# Glucose_Meter_Rev1.net
KiCad netlist of a schematic drawn in EAGLE
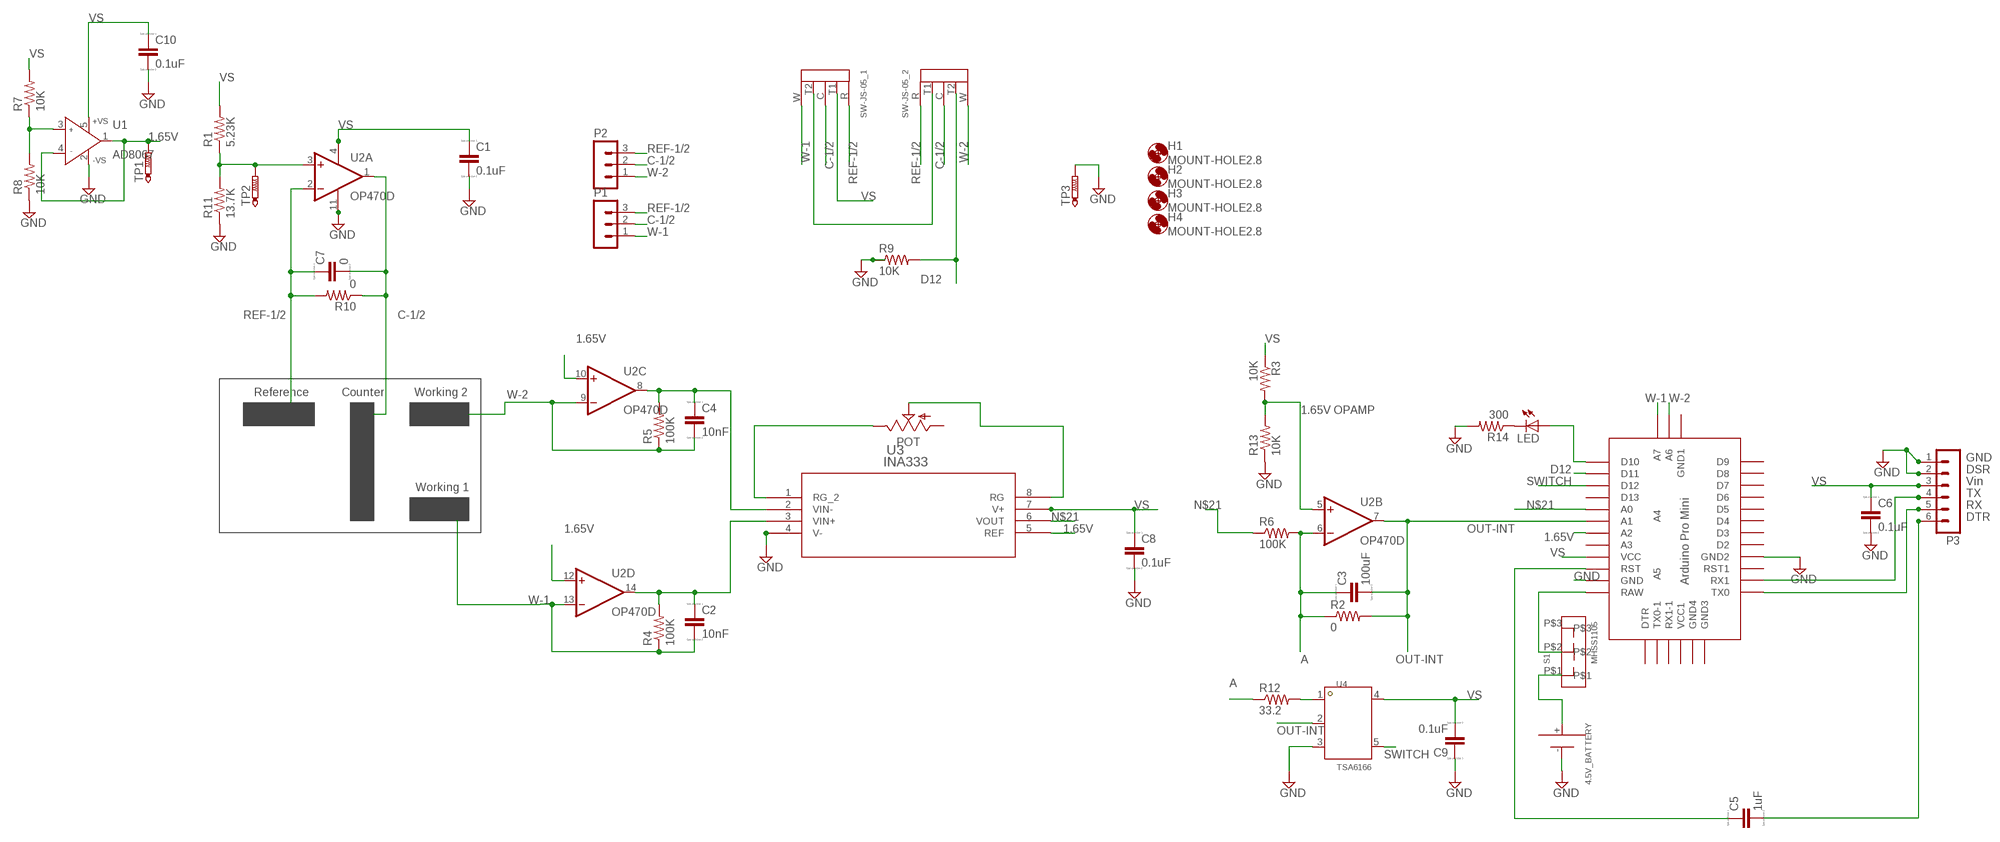
[diagram p0: schematic, sheet 1]

(export (version "E")
  (design (tool "Eeschema 10.0.6"))
  (components
    (comp (ref "4.5V_BATTERY")
      (value "BC3AAAPC")
      (footprint "eagle-import:BC3AAAPC")
      (libsource (lib "eagle-import") (part "BC3AAAPC"))
    )
    (comp (ref "C1")
      (value "0.1uF")
      (footprint "eagle-import:C0805")
      (libsource (lib "eagle-import") (part "C"))
    )
    (comp (ref "C2")
      (value "10nF")
      (footprint "eagle-import:C0805")
      (libsource (lib "eagle-import") (part "C"))
    )
    (comp (ref "C3")
      (value "100uF")
      (footprint "eagle-import:C1210")
      (libsource (lib "eagle-import") (part "CC1210"))
    )
    (comp (ref "C4")
      (value "10nF")
      (footprint "eagle-import:C0805")
      (libsource (lib "eagle-import") (part "C"))
    )
    (comp (ref "C5")
      (value "1uF")
      (footprint "eagle-import:C0805")
      (libsource (lib "eagle-import") (part "C"))
    )
    (comp (ref "C6")
      (value "0.1uF")
      (footprint "eagle-import:C0805")
      (libsource (lib "eagle-import") (part "C"))
    )
    (comp (ref "C7") (value "0") (footprint "eagle-import:C0805") (libsource (lib "eagle-import") (part "C")))
    (comp (ref "C8")
      (value "0.1uF")
      (footprint "eagle-import:C0805")
      (libsource (lib "eagle-import") (part "C"))
    )
    (comp (ref "C9")
      (value "0.1uF")
      (footprint "eagle-import:C0805")
      (libsource (lib "eagle-import") (part "C"))
    )
    (comp (ref "C10")
      (value "0.1uF")
      (footprint "eagle-import:C0805")
      (libsource (lib "eagle-import") (part "C"))
    )
    (comp (ref "H1")
      (value "MOUNT-HOLE2.8")
      (footprint "eagle-import:2,8")
      (libsource (lib "eagle-import") (part "MOUNT-HOLE2.8"))
    )
    (comp (ref "H2")
      (value "MOUNT-HOLE2.8")
      (footprint "eagle-import:2,8")
      (libsource (lib "eagle-import") (part "MOUNT-HOLE2.8"))
    )
    (comp (ref "H3")
      (value "MOUNT-HOLE2.8")
      (footprint "eagle-import:2,8")
      (libsource (lib "eagle-import") (part "MOUNT-HOLE2.8"))
    )
    (comp (ref "H4")
      (value "MOUNT-HOLE2.8")
      (footprint "eagle-import:2,8")
      (libsource (lib "eagle-import") (part "MOUNT-HOLE2.8"))
    )
    (comp (ref "LED")
      (value "LED3MM")
      (footprint "eagle-import:LED3MM")
      (libsource (lib "eagle-import") (part "LED3MM"))
    )
    (comp (ref "P1")
      (value "MA03-1")
      (footprint "eagle-import:MA03-1")
      (libsource (lib "eagle-import") (part "MA03-1"))
    )
    (comp (ref "P2")
      (value "MA03-1")
      (footprint "eagle-import:MA03-1")
      (libsource (lib "eagle-import") (part "MA03-1"))
    )
    (comp (ref "P3")
      (value "MA06-1")
      (footprint "eagle-import:MA06-1")
      (libsource (lib "eagle-import") (part "MA06-1"))
    )
    (comp (ref "POT")
      (value "TRIM_US-RJ9W")
      (footprint "eagle-import:RJ9W")
      (libsource (lib "eagle-import") (part "TRIM_US-RJ9W"))
    )
    (comp (ref "R1")
      (value "5.23K")
      (footprint "eagle-import:R0805")
      (libsource (lib "eagle-import") (part "R-US_R0805"))
    )
    (comp (ref "R2")
      (value "0")
      (footprint "eagle-import:R0805")
      (libsource (lib "eagle-import") (part "R-US_R0805"))
    )
    (comp (ref "R3")
      (value "10K")
      (footprint "eagle-import:R0805")
      (libsource (lib "eagle-import") (part "R-US_R0805"))
    )
    (comp (ref "R4")
      (value "100K")
      (footprint "eagle-import:R0805")
      (libsource (lib "eagle-import") (part "R-US_R0805"))
    )
    (comp (ref "R5")
      (value "100K")
      (footprint "eagle-import:R0805")
      (libsource (lib "eagle-import") (part "R-US_R0805"))
    )
    (comp (ref "R6")
      (value "100K")
      (footprint "eagle-import:R0805")
      (libsource (lib "eagle-import") (part "R-US_R0805"))
    )
    (comp (ref "R7")
      (value "10K")
      (footprint "eagle-import:R0805")
      (libsource (lib "eagle-import") (part "R-US_R0805"))
    )
    (comp (ref "R8")
      (value "10K")
      (footprint "eagle-import:R0805")
      (libsource (lib "eagle-import") (part "R-US_R0805"))
    )
    (comp (ref "R9")
      (value "10K")
      (footprint "eagle-import:R0805")
      (libsource (lib "eagle-import") (part "R-US_R0805"))
    )
    (comp (ref "R10")
      (value "0")
      (footprint "eagle-import:R0805")
      (libsource (lib "eagle-import") (part "R-US_R0805"))
    )
    (comp (ref "R11")
      (value "13.7K")
      (footprint "eagle-import:R0805")
      (libsource (lib "eagle-import") (part "R-US_R0805"))
    )
    (comp (ref "R12")
      (value "33.2")
      (footprint "eagle-import:R0805")
      (libsource (lib "eagle-import") (part "R-US_R0805"))
    )
    (comp (ref "R13")
      (value "10K")
      (footprint "eagle-import:R0805")
      (libsource (lib "eagle-import") (part "R-US_R0805"))
    )
    (comp (ref "R14")
      (value "300")
      (footprint "eagle-import:R0805")
      (libsource (lib "eagle-import") (part "R-US_R0805"))
    )
    (comp (ref "S1")
      (value "MHSS1105")
      (footprint "eagle-import:MHSS1105")
      (libsource (lib "eagle-import") (part "MHSS1105"))
    )
    (comp (ref "SW-JS-05_1")
      (value "SW-JS-05")
      (footprint "eagle-import:SW-JS-05")
      (libsource (lib "eagle-import") (part "SW-JS-05"))
    )
    (comp (ref "SW-JS-05_2")
      (value "SW-JS-05")
      (footprint "eagle-import:SW-JS-05")
      (libsource (lib "eagle-import") (part "SW-JS-05"))
    )
    (comp (ref "TP1")
      (value "PTR1PAD1-13")
      (footprint "eagle-import:P1-13")
      (libsource (lib "eagle-import") (part "PTR1PAD1-13"))
    )
    (comp (ref "TP2")
      (value "PTR1PAD1-13")
      (footprint "eagle-import:P1-13")
      (libsource (lib "eagle-import") (part "PTR1PAD1-13"))
    )
    (comp (ref "TP3")
      (value "PTR1PAD1-13")
      (footprint "eagle-import:P1-13")
      (libsource (lib "eagle-import") (part "PTR1PAD1-13"))
    )
    (comp (ref "U$1")
      (value "ABK-PRO-MINI")
      (footprint "eagle-import:ABK-PRO-MINI")
      (libsource (lib "eagle-import") (part "ABK-PRO-MINI"))
    )
    (comp (ref "U1")
      (value "AD8067")
      (footprint "eagle-import:SOT23-5")
      (fields (field (name "MF") "ALTERA CORPORATION") (field (name "MPN") "AD8067ARTZ-REEL7"))
      (libsource (lib "eagle-import") (part "AD8067"))
    )
    (comp (ref "U2")
      (value "OP470D")
      (footprint "eagle-import:SO14")
      (libsource (lib "eagle-import") (part "OP470D"))
    )
    (comp (ref "U3")
      (value "INA333")
      (footprint "eagle-import:DGK8")
      (fields
        (field (name "MANUFACTURER") "Texas Instruments")
        (field (name "MANUFACTURER_PART_NUMBER") "ina333_dgk_8")
      )
      (libsource (lib "eagle-import") (part "INA333_DGK_8"))
    )
    (comp (ref "U4")
      (value "TSA6166")
      (footprint "eagle-import:SOT23-5")
      (libsource (lib "eagle-import") (part "TSA6166"))
    )
  )
  (nets
    (net (code "1") (name "/1.65V") (class "Default")
      (node (ref "TP1") (pin "TP") (pinfunction "TP_TP") (pintype "input"))
      (node (ref "U$1") (pin "A2") (pinfunction "A2_A2") (pintype "bidirectional"))
      (node (ref "U1") (pin "1") (pinfunction "OUT_1") (pintype "output"))
      (node (ref "U1") (pin "4") (pinfunction "IN-_4") (pintype "input"))
      (node (ref "U2") (pin "10") (pinfunction "+IN_10") (pintype "input"))
      (node (ref "U2") (pin "12") (pinfunction "+IN_12") (pintype "input"))
      (node (ref "U3") (pin "5") (pinfunction "REF_5") (pintype "passive"))
    )
    (net (code "2") (name "/A") (class "Default")
      (node (ref "C3") (pin "1") (pinfunction "1_1") (pintype "passive"))
      (node (ref "R12") (pin "1") (pinfunction "1_1") (pintype "passive"))
      (node (ref "R2") (pin "1") (pinfunction "1_1") (pintype "passive"))
      (node (ref "R6") (pin "2") (pinfunction "2_2") (pintype "passive"))
      (node (ref "U2") (pin "6") (pinfunction "-IN_6") (pintype "input"))
    )
    (net (code "3") (name "/C-1{slash}2") (class "Default")
      (node (ref "C7") (pin "2") (pinfunction "2_2") (pintype "passive"))
      (node (ref "P1") (pin "2") (pinfunction "2_2") (pintype "passive"))
      (node (ref "P2") (pin "2") (pinfunction "2_2") (pintype "passive"))
      (node (ref "R10") (pin "1") (pinfunction "1_1") (pintype "passive"))
      (node (ref "SW-JS-05_1") (pin "C") (pinfunction "C_C") (pintype "bidirectional"))
      (node (ref "SW-JS-05_2") (pin "C") (pinfunction "C_C") (pintype "bidirectional"))
      (node (ref "U2") (pin "1") (pinfunction "OUT_1") (pintype "output"))
    )
    (net (code "4") (name "/D12") (class "Default")
      (node (ref "R9") (pin "2") (pinfunction "2_2") (pintype "passive"))
      (node (ref "SW-JS-05_2") (pin "T2") (pinfunction "T2_T2") (pintype "bidirectional"))
      (node (ref "U$1") (pin "D11") (pinfunction "D11_D11") (pintype "bidirectional"))
    )
    (net (code "5") (name "/N$21") (class "Default")
      (node (ref "R6") (pin "1") (pinfunction "1_1") (pintype "passive"))
      (node (ref "U$1") (pin "A0") (pinfunction "A0_A0") (pintype "bidirectional"))
      (node (ref "U3") (pin "6") (pinfunction "VOUT_6") (pintype "output"))
    )
    (net (code "6") (name "/OUT-INT") (class "Default")
      (node (ref "C3") (pin "2") (pinfunction "2_2") (pintype "passive"))
      (node (ref "R2") (pin "2") (pinfunction "2_2") (pintype "passive"))
      (node (ref "U$1") (pin "A1") (pinfunction "A1_A1") (pintype "bidirectional"))
      (node (ref "U2") (pin "7") (pinfunction "OUT_7") (pintype "output"))
      (node (ref "U4") (pin "2") (pinfunction "B_2") (pintype "bidirectional"))
    )
    (net (code "7") (name "/REF-1{slash}2") (class "Default")
      (node (ref "C7") (pin "1") (pinfunction "1_1") (pintype "passive"))
      (node (ref "P1") (pin "3") (pinfunction "3_3") (pintype "passive"))
      (node (ref "P2") (pin "3") (pinfunction "3_3") (pintype "passive"))
      (node (ref "R10") (pin "2") (pinfunction "2_2") (pintype "passive"))
      (node (ref "SW-JS-05_1") (pin "R") (pinfunction "R_R") (pintype "bidirectional"))
      (node (ref "SW-JS-05_2") (pin "R") (pinfunction "R_R") (pintype "bidirectional"))
      (node (ref "U2") (pin "2") (pinfunction "-IN_2") (pintype "input"))
    )
    (net (code "8") (name "/SWITCH") (class "Default")
      (node (ref "U$1") (pin "D12") (pinfunction "D12_D12") (pintype "bidirectional"))
      (node (ref "U4") (pin "5") (pinfunction "ON/OFF_5") (pintype "bidirectional"))
    )
    (net (code "9") (name "/VS") (class "Default")
      (node (ref "C1") (pin "1") (pinfunction "1_1") (pintype "passive"))
      (node (ref "C10") (pin "1") (pinfunction "1_1") (pintype "passive"))
      (node (ref "C6") (pin "1") (pinfunction "1_1") (pintype "passive"))
      (node (ref "C8") (pin "1") (pinfunction "1_1") (pintype "passive"))
      (node (ref "C9") (pin "2") (pinfunction "2_2") (pintype "passive"))
      (node (ref "P3") (pin "3") (pinfunction "3_3") (pintype "passive"))
      (node (ref "R1") (pin "2") (pinfunction "2_2") (pintype "passive"))
      (node (ref "R3") (pin "1") (pinfunction "1_1") (pintype "passive"))
      (node (ref "R7") (pin "2") (pinfunction "2_2") (pintype "passive"))
      (node (ref "SW-JS-05_1") (pin "T1") (pinfunction "T1_T1") (pintype "bidirectional"))
      (node (ref "U$1") (pin "VCC") (pinfunction "VCC_VCC") (pintype "bidirectional"))
      (node (ref "U1") (pin "5") (pinfunction "+VS_5") (pintype "input"))
      (node (ref "U2") (pin "4") (pinfunction "V+_4") (pintype "power_in"))
      (node (ref "U3") (pin "7") (pinfunction "V+_7") (pintype "power_in"))
      (node (ref "U4") (pin "4") (pinfunction "VS_4") (pintype "bidirectional"))
    )
    (net (code "10") (name "/W-1") (class "Default")
      (node (ref "C2") (pin "2") (pinfunction "2_2") (pintype "passive"))
      (node (ref "P1") (pin "1") (pinfunction "1_1") (pintype "passive"))
      (node (ref "R4") (pin "1") (pinfunction "1_1") (pintype "passive"))
      (node (ref "SW-JS-05_1") (pin "W") (pinfunction "W_W") (pintype "bidirectional"))
      (node (ref "U$1") (pin "A7") (pinfunction "A7_A7") (pintype "bidirectional"))
      (node (ref "U2") (pin "13") (pinfunction "-IN_13") (pintype "input"))
    )
    (net (code "11") (name "/W-2") (class "Default")
      (node (ref "C4") (pin "2") (pinfunction "2_2") (pintype "passive"))
      (node (ref "P2") (pin "1") (pinfunction "1_1") (pintype "passive"))
      (node (ref "R5") (pin "1") (pinfunction "1_1") (pintype "passive"))
      (node (ref "SW-JS-05_2") (pin "W") (pinfunction "W_W") (pintype "bidirectional"))
      (node (ref "U$1") (pin "A6") (pinfunction "A6_A6") (pintype "bidirectional"))
      (node (ref "U2") (pin "9") (pinfunction "-IN_9") (pintype "input"))
    )
    (net (code "12") (name "GND") (class "Default")
      (node (ref "4.5V_BATTERY") (pin "-") (pinfunction "-_-") (pintype "bidirectional"))
      (node (ref "C1") (pin "2") (pinfunction "2_2") (pintype "passive"))
      (node (ref "C10") (pin "2") (pinfunction "2_2") (pintype "passive"))
      (node (ref "C6") (pin "2") (pinfunction "2_2") (pintype "passive"))
      (node (ref "C8") (pin "2") (pinfunction "2_2") (pintype "passive"))
      (node (ref "C9") (pin "1") (pinfunction "1_1") (pintype "passive"))
      (node (ref "P3") (pin "1") (pinfunction "1_1") (pintype "passive"))
      (node (ref "P3") (pin "2") (pinfunction "2_2") (pintype "passive"))
      (node (ref "R11") (pin "1") (pinfunction "1_1") (pintype "passive"))
      (node (ref "R13") (pin "1") (pinfunction "1_1") (pintype "passive"))
      (node (ref "R14") (pin "2") (pinfunction "2_2") (pintype "passive"))
      (node (ref "R8") (pin "1") (pinfunction "1_1") (pintype "passive"))
      (node (ref "R9") (pin "1") (pinfunction "1_1") (pintype "passive"))
      (node (ref "TP3") (pin "TP") (pinfunction "TP_TP") (pintype "input"))
      (node (ref "U$1") (pin "GND") (pinfunction "GND_GND") (pintype "bidirectional"))
      (node (ref "U$1") (pin "GND1") (pinfunction "GND2_GND1") (pintype "bidirectional"))
      (node (ref "U1") (pin "2") (pinfunction "-VS_2") (pintype "input"))
      (node (ref "U2") (pin "11") (pinfunction "V-_11") (pintype "power_in"))
      (node (ref "U3") (pin "4") (pinfunction "V-_4") (pintype "power_in"))
      (node (ref "U4") (pin "3") (pinfunction "GND_3") (pintype "bidirectional"))
    )
    (net (code "13") (name "Net-(4.5V_BATTERY-Pad+)") (class "Default")
      (node (ref "4.5V_BATTERY") (pin "+") (pinfunction "+_+") (pintype "bidirectional"))
      (node (ref "S1") (pin "P$1") (pinfunction "P$1_P$1") (pintype "bidirectional"))
    )
    (net (code "14") (name "Net-(C5-Pad1)") (class "Default")
      (node (ref "C5") (pin "1") (pinfunction "1_1") (pintype "passive"))
      (node (ref "U$1") (pin "RST") (pinfunction "RST_RST") (pintype "bidirectional"))
    )
    (net (code "15") (name "Net-(C5-Pad2)") (class "Default")
      (node (ref "C5") (pin "2") (pinfunction "2_2") (pintype "passive"))
      (node (ref "P3") (pin "6") (pinfunction "6_6") (pintype "passive"))
    )
    (net (code "16") (name "Net-(LED-C)") (class "Default")
      (node (ref "LED") (pin "K") (pinfunction "C_K") (pintype "passive"))
      (node (ref "R14") (pin "1") (pinfunction "1_1") (pintype "passive"))
    )
    (net (code "17") (name "Net-(LED-PadA)") (class "Default")
      (node (ref "LED") (pin "A") (pinfunction "A_A") (pintype "passive"))
      (node (ref "U$1") (pin "D10") (pinfunction "D10_D10") (pintype "bidirectional"))
    )
    (net (code "18") (name "Net-(P3-Pad4)") (class "Default")
      (node (ref "P3") (pin "4") (pinfunction "4_4") (pintype "passive"))
      (node (ref "U$1") (pin "RX1") (pinfunction "RX1_RX1") (pintype "bidirectional"))
    )
    (net (code "19") (name "Net-(P3-Pad5)") (class "Default")
      (node (ref "P3") (pin "5") (pinfunction "5_5") (pintype "passive"))
      (node (ref "U$1") (pin "TX0") (pinfunction "TX0_TX0") (pintype "bidirectional"))
    )
    (net (code "20") (name "Net-(S1-PadP$2)") (class "Default")
      (node (ref "S1") (pin "P$2") (pinfunction "P$2_P$2") (pintype "bidirectional"))
      (node (ref "U$1") (pin "RAW") (pinfunction "RAW_RAW") (pintype "bidirectional"))
    )
    (net (code "21") (name "Net-(SW-JS-05_1-PadT2)") (class "Default")
      (node (ref "SW-JS-05_1") (pin "T2") (pinfunction "T2_T2") (pintype "bidirectional"))
      (node (ref "SW-JS-05_2") (pin "T1") (pinfunction "T1_T1") (pintype "bidirectional"))
    )
    (net (code "22") (name "Net-(U1-IN+)") (class "Default")
      (node (ref "R7") (pin "1") (pinfunction "1_1") (pintype "passive"))
      (node (ref "R8") (pin "2") (pinfunction "2_2") (pintype "passive"))
      (node (ref "U1") (pin "3") (pinfunction "IN+_3") (pintype "input"))
    )
    (net (code "23") (name "Net-(U2A-+IN)") (class "Default")
      (node (ref "R1") (pin "1") (pinfunction "1_1") (pintype "passive"))
      (node (ref "R11") (pin "2") (pinfunction "2_2") (pintype "passive"))
      (node (ref "TP2") (pin "TP") (pinfunction "TP_TP") (pintype "input"))
      (node (ref "U2") (pin "3") (pinfunction "+IN_3") (pintype "input"))
    )
    (net (code "24") (name "Net-(U2B-+IN)") (class "Default")
      (node (ref "R13") (pin "2") (pinfunction "2_2") (pintype "passive"))
      (node (ref "R3") (pin "2") (pinfunction "2_2") (pintype "passive"))
      (node (ref "U2") (pin "5") (pinfunction "+IN_5") (pintype "input"))
    )
    (net (code "25") (name "Net-(U2C-OUT)") (class "Default")
      (node (ref "C4") (pin "1") (pinfunction "1_1") (pintype "passive"))
      (node (ref "R5") (pin "2") (pinfunction "2_2") (pintype "passive"))
      (node (ref "U2") (pin "8") (pinfunction "OUT_8") (pintype "output"))
      (node (ref "U3") (pin "2") (pinfunction "VIN-_2") (pintype "input"))
    )
    (net (code "26") (name "Net-(U2D-OUT)") (class "Default")
      (node (ref "C2") (pin "1") (pinfunction "1_1") (pintype "passive"))
      (node (ref "R4") (pin "2") (pinfunction "2_2") (pintype "passive"))
      (node (ref "U2") (pin "14") (pinfunction "OUT_14") (pintype "output"))
      (node (ref "U3") (pin "3") (pinfunction "VIN+_3") (pintype "input"))
    )
    (net (code "27") (name "Net-(U3-RG)") (class "Default")
      (node (ref "POT") (pin "S") (pinfunction "S_S") (pintype "passive"))
      (node (ref "U3") (pin "8") (pinfunction "RG_8") (pintype "passive"))
    )
    (net (code "28") (name "Net-(U3-RG_2)") (class "Default")
      (node (ref "POT") (pin "E") (pinfunction "E_E") (pintype "passive"))
      (node (ref "U3") (pin "1") (pinfunction "RG_2_1") (pintype "passive"))
    )
    (net (code "29") (name "Net-(U4-A)") (class "Default")
      (node (ref "R12") (pin "2") (pinfunction "2_2") (pintype "passive"))
      (node (ref "U4") (pin "1") (pinfunction "A_1") (pintype "bidirectional"))
    )
    (net (code "30") (name "unconnected-(POT-PadA)") (class "Default")
      (node (ref "POT") (pin "A") (pinfunction "A_A") (pintype "passive"))
    )
    (net (code "31") (name "unconnected-(S1-PadP$3)") (class "Default")
      (node (ref "S1") (pin "P$3") (pinfunction "P$3_P$3") (pintype "bidirectional"))
    )
    (net (code "32") (name "unconnected-(U$1-GND1-PadGND4)") (class "Default")
      (node (ref "U$1") (pin "GND4") (pinfunction "GND1_GND4") (pintype "bidirectional"))
    )
    (net (code "33") (name "unconnected-(U$1-GND3-PadGND2)") (class "Default")
      (node (ref "U$1") (pin "GND2") (pinfunction "GND3_GND2") (pintype "bidirectional"))
    )
    (net (code "34") (name "unconnected-(U$1-GND4-PadGND3)") (class "Default")
      (node (ref "U$1") (pin "GND3") (pinfunction "GND4_GND3") (pintype "bidirectional"))
    )
    (net (code "35") (name "unconnected-(U$1-PadA3)") (class "Default")
      (node (ref "U$1") (pin "A3") (pinfunction "A3_A3") (pintype "bidirectional"))
    )
    (net (code "36") (name "unconnected-(U$1-PadA4)") (class "Default")
      (node (ref "U$1") (pin "A4") (pinfunction "A4_A4") (pintype "bidirectional"))
    )
    (net (code "37") (name "unconnected-(U$1-PadA5)") (class "Default")
      (node (ref "U$1") (pin "A5") (pinfunction "A5_A5") (pintype "bidirectional"))
    )
    (net (code "38") (name "unconnected-(U$1-PadD2)") (class "Default")
      (node (ref "U$1") (pin "D2") (pinfunction "D2_D2") (pintype "bidirectional"))
    )
    (net (code "39") (name "unconnected-(U$1-PadD3)") (class "Default")
      (node (ref "U$1") (pin "D3") (pinfunction "D3_D3") (pintype "bidirectional"))
    )
    (net (code "40") (name "unconnected-(U$1-PadD4)") (class "Default")
      (node (ref "U$1") (pin "D4") (pinfunction "D4_D4") (pintype "bidirectional"))
    )
    (net (code "41") (name "unconnected-(U$1-PadD5)") (class "Default")
      (node (ref "U$1") (pin "D5") (pinfunction "D5_D5") (pintype "bidirectional"))
    )
    (net (code "42") (name "unconnected-(U$1-PadD6)") (class "Default")
      (node (ref "U$1") (pin "D6") (pinfunction "D6_D6") (pintype "bidirectional"))
    )
    (net (code "43") (name "unconnected-(U$1-PadD7)") (class "Default")
      (node (ref "U$1") (pin "D7") (pinfunction "D7_D7") (pintype "bidirectional"))
    )
    (net (code "44") (name "unconnected-(U$1-PadD8)") (class "Default")
      (node (ref "U$1") (pin "D8") (pinfunction "D8_D8") (pintype "bidirectional"))
    )
    (net (code "45") (name "unconnected-(U$1-PadD9)") (class "Default")
      (node (ref "U$1") (pin "D9") (pinfunction "D9_D9") (pintype "bidirectional"))
    )
    (net (code "46") (name "unconnected-(U$1-PadD13)") (class "Default")
      (node (ref "U$1") (pin "D13") (pinfunction "D13_D13") (pintype "bidirectional"))
    )
    (net (code "47") (name "unconnected-(U$1-PadDTR)") (class "Default")
      (node (ref "U$1") (pin "DTR") (pinfunction "DTR_DTR") (pintype "bidirectional"))
    )
    (net (code "48") (name "unconnected-(U$1-PadRST1)") (class "Default")
      (node (ref "U$1") (pin "RST1") (pinfunction "RST1_RST1") (pintype "bidirectional"))
    )
    (net (code "49") (name "unconnected-(U$1-PadRX1-1)") (class "Default")
      (node (ref "U$1") (pin "RX1-1") (pinfunction "RX1-1_RX1-1") (pintype "bidirectional"))
    )
    (net (code "50") (name "unconnected-(U$1-PadTX0-1)") (class "Default")
      (node (ref "U$1") (pin "TX0-1") (pinfunction "TX0-1_TX0-1") (pintype "bidirectional"))
    )
    (net (code "51") (name "unconnected-(U$1-PadVCC1)") (class "Default")
      (node (ref "U$1") (pin "VCC1") (pinfunction "VCC1_VCC1") (pintype "bidirectional"))
    )
  )
)
